# ZynqPower.net
KiCad netlist of a schematic drawn in Altium Designer
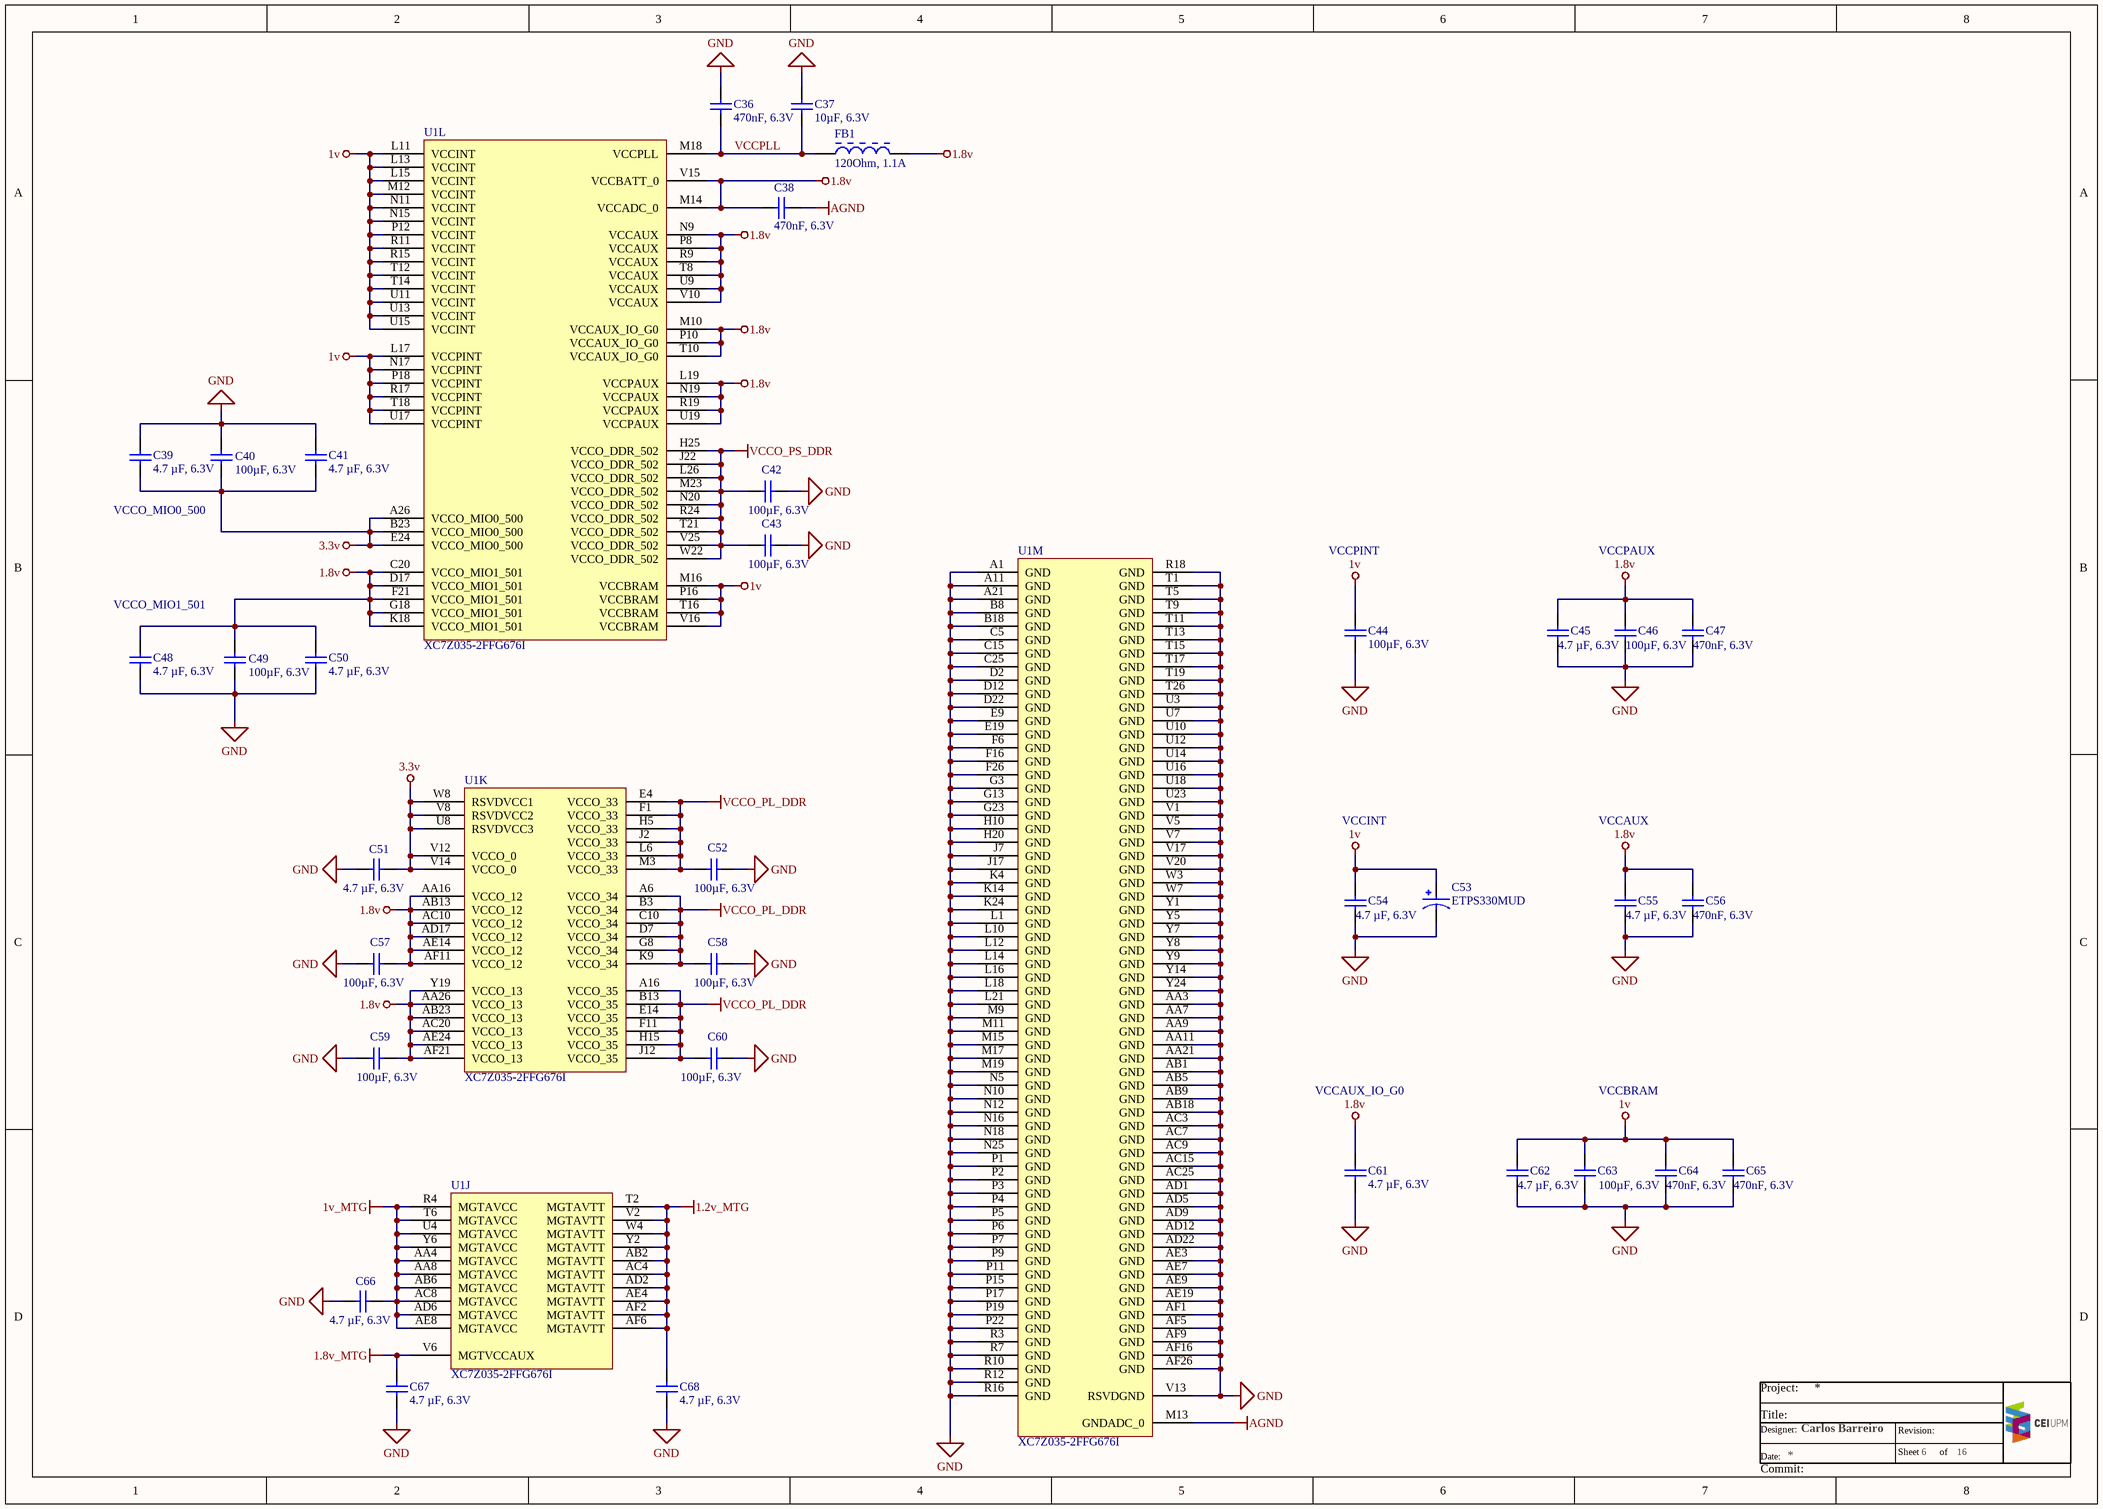
[diagram p0: ZynqPower.SchDoc]

(export (version "E")
  (design (tool "Eeschema 10.0.6"))
  (components
    (comp (ref "C36")
      (value "470nF, 6.3V")
      (footprint "WURTH_WCAP-CSGP_0402")
      (description "WCAP-CSGP Multilayer Ceramic Chip Capacitor, General Purpose, size 0402, X5R, 470nF, 6.3V")
      (fields
        (field (name "MANUFACTURER PART NUMBER") "885012105004")
        (field (name "MANUFACTURER") "Wurth Elektronik")
      )
      (libsource (lib "SpaceVNX") (part "885012105004"))
    )
    (comp (ref "C37")
      (value "10µF, 6.3V")
      (footprint "WURTH_WCAP-CSGP_0402")
      (description "WCAP-CSGP Multilayer Ceramic Chip Capacitor, General Purpose, size 0402, X5R, 10uF, 6.3V")
      (fields
        (field (name "MANUFACTURER PART NUMBER") "885012105020")
        (field (name "MANUFACTURER") "Wurth Elektronik")
      )
      (libsource (lib "SpaceVNX") (part "885012105020"))
    )
    (comp (ref "C38")
      (value "470nF, 6.3V")
      (footprint "WURTH_WCAP-CSGP_0402")
      (description "WCAP-CSGP Multilayer Ceramic Chip Capacitor, General Purpose, size 0402, X5R, 470nF, 6.3V")
      (fields
        (field (name "MANUFACTURER PART NUMBER") "885012105004")
        (field (name "MANUFACTURER") "Wurth Elektronik")
      )
      (libsource (lib "SpaceVNX") (part "885012105004"))
    )
    (comp (ref "C39")
      (value "4.7 µF, 6.3V")
      (footprint "WURTH_WCAP-CSGP_0402")
      (description "Multilayer Ceramic Capacitors MLCC, size 0402, X5R, 4.7 µF, 6.3V")
      (fields
        (field (name "MANUFACTURER PART NUMBER") "GRM155C80J475MEAAD")
        (field (name "MANUFACTURER") "Murata")
      )
      (libsource (lib "SpaceVNX") (part "GRM155C80J475MEAAD"))
    )
    (comp (ref "C40")
      (value "100µF, 6.3V")
      (footprint "WURTH_WCAP-CSGP_1206_H=1.6mm")
      (description "WCAP-CSGP Multilayer Ceramic Chip Capacitor, General Purpose, size 1206, X5R, 100uF, 6.3V")
      (fields
        (field (name "MANUFACTURER PART NUMBER") "885012108005")
        (field (name "MANUFACTURER") "Wurth Elektronik")
      )
      (libsource (lib "SpaceVNX") (part "885012108005"))
    )
    (comp (ref "C41")
      (value "4.7 µF, 6.3V")
      (footprint "WURTH_WCAP-CSGP_0402")
      (description "Multilayer Ceramic Capacitors MLCC, size 0402, X5R, 4.7 µF, 6.3V")
      (fields
        (field (name "MANUFACTURER PART NUMBER") "GRM155C80J475MEAAD")
        (field (name "MANUFACTURER") "Murata")
      )
      (libsource (lib "SpaceVNX") (part "GRM155C80J475MEAAD"))
    )
    (comp (ref "C42")
      (value "100µF, 6.3V")
      (footprint "WURTH_WCAP-CSGP_1206_H=1.6mm")
      (description "WCAP-CSGP Multilayer Ceramic Chip Capacitor, General Purpose, size 1206, X5R, 100uF, 6.3V")
      (fields
        (field (name "MANUFACTURER PART NUMBER") "885012108005")
        (field (name "MANUFACTURER") "Wurth Elektronik")
      )
      (libsource (lib "SpaceVNX") (part "885012108005"))
    )
    (comp (ref "C43")
      (value "100µF, 6.3V")
      (footprint "WURTH_WCAP-CSGP_1206_H=1.6mm")
      (description "WCAP-CSGP Multilayer Ceramic Chip Capacitor, General Purpose, size 1206, X5R, 100uF, 6.3V")
      (fields
        (field (name "MANUFACTURER PART NUMBER") "885012108005")
        (field (name "MANUFACTURER") "Wurth Elektronik")
      )
      (libsource (lib "SpaceVNX") (part "885012108005"))
    )
    (comp (ref "C44")
      (value "100µF, 6.3V")
      (footprint "WURTH_WCAP-CSGP_1206_H=1.6mm")
      (description "WCAP-CSGP Multilayer Ceramic Chip Capacitor, General Purpose, size 1206, X5R, 100uF, 6.3V")
      (fields
        (field (name "MANUFACTURER PART NUMBER") "885012108005")
        (field (name "MANUFACTURER") "Wurth Elektronik")
      )
      (libsource (lib "SpaceVNX") (part "885012108005"))
    )
    (comp (ref "C45")
      (value "4.7 µF, 6.3V")
      (footprint "WURTH_WCAP-CSGP_0402")
      (description "Multilayer Ceramic Capacitors MLCC, size 0402, X5R, 4.7 µF, 6.3V")
      (fields
        (field (name "MANUFACTURER PART NUMBER") "GRM155C80J475MEAAD")
        (field (name "MANUFACTURER") "Murata")
      )
      (libsource (lib "SpaceVNX") (part "GRM155C80J475MEAAD"))
    )
    (comp (ref "C46")
      (value "100µF, 6.3V")
      (footprint "WURTH_WCAP-CSGP_1206_H=1.6mm")
      (description "WCAP-CSGP Multilayer Ceramic Chip Capacitor, General Purpose, size 1206, X5R, 100uF, 6.3V")
      (fields
        (field (name "MANUFACTURER PART NUMBER") "885012108005")
        (field (name "MANUFACTURER") "Wurth Elektronik")
      )
      (libsource (lib "SpaceVNX") (part "885012108005"))
    )
    (comp (ref "C47")
      (value "470nF, 6.3V")
      (footprint "WURTH_WCAP-CSGP_0402")
      (description "WCAP-CSGP Multilayer Ceramic Chip Capacitor, General Purpose, size 0402, X5R, 470nF, 6.3V")
      (fields
        (field (name "MANUFACTURER PART NUMBER") "885012105004")
        (field (name "MANUFACTURER") "Wurth Elektronik")
      )
      (libsource (lib "SpaceVNX") (part "885012105004"))
    )
    (comp (ref "C48")
      (value "4.7 µF, 6.3V")
      (footprint "WURTH_WCAP-CSGP_0402")
      (description "Multilayer Ceramic Capacitors MLCC, size 0402, X5R, 4.7 µF, 6.3V")
      (fields
        (field (name "MANUFACTURER PART NUMBER") "GRM155C80J475MEAAD")
        (field (name "MANUFACTURER") "Murata")
      )
      (libsource (lib "SpaceVNX") (part "GRM155C80J475MEAAD"))
    )
    (comp (ref "C49")
      (value "100µF, 6.3V")
      (footprint "WURTH_WCAP-CSGP_1206_H=1.6mm")
      (description "WCAP-CSGP Multilayer Ceramic Chip Capacitor, General Purpose, size 1206, X5R, 100uF, 6.3V")
      (fields
        (field (name "MANUFACTURER PART NUMBER") "885012108005")
        (field (name "MANUFACTURER") "Wurth Elektronik")
      )
      (libsource (lib "SpaceVNX") (part "885012108005"))
    )
    (comp (ref "C50")
      (value "4.7 µF, 6.3V")
      (footprint "WURTH_WCAP-CSGP_0402")
      (description "Multilayer Ceramic Capacitors MLCC, size 0402, X5R, 4.7 µF, 6.3V")
      (fields
        (field (name "MANUFACTURER PART NUMBER") "GRM155C80J475MEAAD")
        (field (name "MANUFACTURER") "Murata")
      )
      (libsource (lib "SpaceVNX") (part "GRM155C80J475MEAAD"))
    )
    (comp (ref "C51")
      (value "4.7 µF, 6.3V")
      (footprint "WURTH_WCAP-CSGP_0402")
      (description "Multilayer Ceramic Capacitors MLCC, size 0402, X5R, 4.7 µF, 6.3V")
      (fields
        (field (name "MANUFACTURER PART NUMBER") "GRM155C80J475MEAAD")
        (field (name "MANUFACTURER") "Murata")
      )
      (libsource (lib "SpaceVNX") (part "GRM155C80J475MEAAD"))
    )
    (comp (ref "C52")
      (value "100µF, 6.3V")
      (footprint "WURTH_WCAP-CSGP_1206_H=1.6mm")
      (description "WCAP-CSGP Multilayer Ceramic Chip Capacitor, General Purpose, size 1206, X5R, 100uF, 6.3V")
      (fields
        (field (name "MANUFACTURER PART NUMBER") "885012108005")
        (field (name "MANUFACTURER") "Wurth Elektronik")
      )
      (libsource (lib "SpaceVNX") (part "885012108005"))
    )
    (comp (ref "C53")
      (value "ETPS330MUD")
      (footprint "PANASONIC_B1S")
      (description "Conductive Polymer Tantalum Solid Capacitors")
      (fields (field (name "MF") "Panasonic"))
      (libsource (lib "SpaceVNX") (part "ETPS330MUD"))
    )
    (comp (ref "C54")
      (value "4.7 µF, 6.3V")
      (footprint "WURTH_WCAP-CSGP_0402")
      (description "Multilayer Ceramic Capacitors MLCC, size 0402, X5R, 4.7 µF, 6.3V")
      (fields
        (field (name "MANUFACTURER PART NUMBER") "GRM155C80J475MEAAD")
        (field (name "MANUFACTURER") "Murata")
      )
      (libsource (lib "SpaceVNX") (part "GRM155C80J475MEAAD"))
    )
    (comp (ref "C55")
      (value "4.7 µF, 6.3V")
      (footprint "WURTH_WCAP-CSGP_0402")
      (description "Multilayer Ceramic Capacitors MLCC, size 0402, X5R, 4.7 µF, 6.3V")
      (fields
        (field (name "MANUFACTURER PART NUMBER") "GRM155C80J475MEAAD")
        (field (name "MANUFACTURER") "Murata")
      )
      (libsource (lib "SpaceVNX") (part "GRM155C80J475MEAAD"))
    )
    (comp (ref "C56")
      (value "470nF, 6.3V")
      (footprint "WURTH_WCAP-CSGP_0402")
      (description "WCAP-CSGP Multilayer Ceramic Chip Capacitor, General Purpose, size 0402, X5R, 470nF, 6.3V")
      (fields
        (field (name "MANUFACTURER PART NUMBER") "885012105004")
        (field (name "MANUFACTURER") "Wurth Elektronik")
      )
      (libsource (lib "SpaceVNX") (part "885012105004"))
    )
    (comp (ref "C57")
      (value "100µF, 6.3V")
      (footprint "WURTH_WCAP-CSGP_1206_H=1.6mm")
      (description "WCAP-CSGP Multilayer Ceramic Chip Capacitor, General Purpose, size 1206, X5R, 100uF, 6.3V")
      (fields
        (field (name "MANUFACTURER PART NUMBER") "885012108005")
        (field (name "MANUFACTURER") "Wurth Elektronik")
      )
      (libsource (lib "SpaceVNX") (part "885012108005"))
    )
    (comp (ref "C58")
      (value "100µF, 6.3V")
      (footprint "WURTH_WCAP-CSGP_1206_H=1.6mm")
      (description "WCAP-CSGP Multilayer Ceramic Chip Capacitor, General Purpose, size 1206, X5R, 100uF, 6.3V")
      (fields
        (field (name "MANUFACTURER PART NUMBER") "885012108005")
        (field (name "MANUFACTURER") "Wurth Elektronik")
      )
      (libsource (lib "SpaceVNX") (part "885012108005"))
    )
    (comp (ref "C59")
      (value "100µF, 6.3V")
      (footprint "WURTH_WCAP-CSGP_1206_H=1.6mm")
      (description "WCAP-CSGP Multilayer Ceramic Chip Capacitor, General Purpose, size 1206, X5R, 100uF, 6.3V")
      (fields
        (field (name "MANUFACTURER PART NUMBER") "885012108005")
        (field (name "MANUFACTURER") "Wurth Elektronik")
      )
      (libsource (lib "SpaceVNX") (part "885012108005"))
    )
    (comp (ref "C60")
      (value "100µF, 6.3V")
      (footprint "WURTH_WCAP-CSGP_1206_H=1.6mm")
      (description "WCAP-CSGP Multilayer Ceramic Chip Capacitor, General Purpose, size 1206, X5R, 100uF, 6.3V")
      (fields
        (field (name "MANUFACTURER PART NUMBER") "885012108005")
        (field (name "MANUFACTURER") "Wurth Elektronik")
      )
      (libsource (lib "SpaceVNX") (part "885012108005"))
    )
    (comp (ref "C61")
      (value "4.7 µF, 6.3V")
      (footprint "WURTH_WCAP-CSGP_0402")
      (description "Multilayer Ceramic Capacitors MLCC, size 0402, X5R, 4.7 µF, 6.3V")
      (fields
        (field (name "MANUFACTURER PART NUMBER") "GRM155C80J475MEAAD")
        (field (name "MANUFACTURER") "Murata")
      )
      (libsource (lib "SpaceVNX") (part "GRM155C80J475MEAAD"))
    )
    (comp (ref "C62")
      (value "4.7 µF, 6.3V")
      (footprint "WURTH_WCAP-CSGP_0402")
      (description "Multilayer Ceramic Capacitors MLCC, size 0402, X5R, 4.7 µF, 6.3V")
      (fields
        (field (name "MANUFACTURER PART NUMBER") "GRM155C80J475MEAAD")
        (field (name "MANUFACTURER") "Murata")
      )
      (libsource (lib "SpaceVNX") (part "GRM155C80J475MEAAD"))
    )
    (comp (ref "C63")
      (value "100µF, 6.3V")
      (footprint "WURTH_WCAP-CSGP_1206_H=1.6mm")
      (description "WCAP-CSGP Multilayer Ceramic Chip Capacitor, General Purpose, size 1206, X5R, 100uF, 6.3V")
      (fields
        (field (name "MANUFACTURER PART NUMBER") "885012108005")
        (field (name "MANUFACTURER") "Wurth Elektronik")
      )
      (libsource (lib "SpaceVNX") (part "885012108005"))
    )
    (comp (ref "C64")
      (value "470nF, 6.3V")
      (footprint "WURTH_WCAP-CSGP_0402")
      (description "WCAP-CSGP Multilayer Ceramic Chip Capacitor, General Purpose, size 0402, X5R, 470nF, 6.3V")
      (fields
        (field (name "MANUFACTURER PART NUMBER") "885012105004")
        (field (name "MANUFACTURER") "Wurth Elektronik")
      )
      (libsource (lib "SpaceVNX") (part "885012105004"))
    )
    (comp (ref "C65")
      (value "470nF, 6.3V")
      (footprint "WURTH_WCAP-CSGP_0402")
      (description "WCAP-CSGP Multilayer Ceramic Chip Capacitor, General Purpose, size 0402, X5R, 470nF, 6.3V")
      (fields
        (field (name "MANUFACTURER PART NUMBER") "885012105004")
        (field (name "MANUFACTURER") "Wurth Elektronik")
      )
      (libsource (lib "SpaceVNX") (part "885012105004"))
    )
    (comp (ref "C66")
      (value "4.7 µF, 6.3V")
      (footprint "WURTH_WCAP-CSGP_0402")
      (description "Multilayer Ceramic Capacitors MLCC, size 0402, X5R, 4.7 µF, 6.3V")
      (fields
        (field (name "MANUFACTURER PART NUMBER") "GRM155C80J475MEAAD")
        (field (name "MANUFACTURER") "Murata")
      )
      (libsource (lib "SpaceVNX") (part "GRM155C80J475MEAAD"))
    )
    (comp (ref "C67")
      (value "4.7 µF, 6.3V")
      (footprint "WURTH_WCAP-CSGP_0402")
      (description "Multilayer Ceramic Capacitors MLCC, size 0402, X5R, 4.7 µF, 6.3V")
      (fields
        (field (name "MANUFACTURER PART NUMBER") "GRM155C80J475MEAAD")
        (field (name "MANUFACTURER") "Murata")
      )
      (libsource (lib "SpaceVNX") (part "GRM155C80J475MEAAD"))
    )
    (comp (ref "C68")
      (value "4.7 µF, 6.3V")
      (footprint "WURTH_WCAP-CSGP_0402")
      (description "Multilayer Ceramic Capacitors MLCC, size 0402, X5R, 4.7 µF, 6.3V")
      (fields
        (field (name "MANUFACTURER PART NUMBER") "GRM155C80J475MEAAD")
        (field (name "MANUFACTURER") "Murata")
      )
      (libsource (lib "SpaceVNX") (part "GRM155C80J475MEAAD"))
    )
    (comp (ref "FB1")
      (value "120Ohm, 1.1A")
      (footprint "WURTH-CBF_0402")
      (description "WE-CBF SMT EMI Suppression Ferrite Bead, size 0402, 120Ohm, 1.1A")
      (fields
        (field (name "MANUFACTURER PART NUMBER") "74279271")
        (field (name "MANUFACTURER") "Wurth Elektronik")
      )
      (libsource (lib "SpaceVNX") (part "74279271"))
    )
    (comp (ref "U1")
      (value "XC7Z035-2FFG676I")
      (footprint "XILINX_FBG676")
      (fields (field (name "PARTNUMBER") "XC7Z035-2FBG676I") (field (name "GENERIC PART NUMBER") "XC7Z035"))
      (libsource (lib "SpaceVNX") (part "XC7Z035-2FFG676I"))
    )
  )
  (nets
    (net (code "1") (name "/VCCPLL") (class "Default")
      (node (ref "C36") (pin "1") (pinfunction "1_1") (pintype "passive"))
      (node (ref "C37") (pin "1") (pinfunction "1_1") (pintype "passive"))
      (node (ref "FB1") (pin "1") (pinfunction "1_1") (pintype "passive"))
      (node (ref "U1") (pin "M18") (pinfunction "VCCPLL_M18") (pintype "power_in"))
    )
    (net (code "2") (name "1.2v_MTG") (class "Default")
      (node (ref "C68") (pin "2") (pinfunction "2_2") (pintype "passive"))
      (node (ref "U1") (pin "AB2") (pinfunction "MGTAVTT_AB2") (pintype "power_in"))
      (node (ref "U1") (pin "AC4") (pinfunction "MGTAVTT_AC4") (pintype "power_in"))
      (node (ref "U1") (pin "AD2") (pinfunction "MGTAVTT_AD2") (pintype "power_in"))
      (node (ref "U1") (pin "AE4") (pinfunction "MGTAVTT_AE4") (pintype "power_in"))
      (node (ref "U1") (pin "AF2") (pinfunction "MGTAVTT_AF2") (pintype "power_in"))
      (node (ref "U1") (pin "AF6") (pinfunction "MGTAVTT_AF6") (pintype "power_in"))
      (node (ref "U1") (pin "T2") (pinfunction "MGTAVTT_T2") (pintype "power_in"))
      (node (ref "U1") (pin "V2") (pinfunction "MGTAVTT_V2") (pintype "power_in"))
      (node (ref "U1") (pin "W4") (pinfunction "MGTAVTT_W4") (pintype "power_in"))
      (node (ref "U1") (pin "Y2") (pinfunction "MGTAVTT_Y2") (pintype "power_in"))
    )
    (net (code "3") (name "1.8v") (class "Default")
      (node (ref "C38") (pin "2") (pinfunction "2_2") (pintype "passive"))
      (node (ref "C45") (pin "1") (pinfunction "1_1") (pintype "passive"))
      (node (ref "C46") (pin "2") (pinfunction "2_2") (pintype "passive"))
      (node (ref "C47") (pin "2") (pinfunction "2_2") (pintype "passive"))
      (node (ref "C48") (pin "2") (pinfunction "2_2") (pintype "passive"))
      (node (ref "C49") (pin "1") (pinfunction "1_1") (pintype "passive"))
      (node (ref "C50") (pin "2") (pinfunction "2_2") (pintype "passive"))
      (node (ref "C55") (pin "2") (pinfunction "2_2") (pintype "passive"))
      (node (ref "C56") (pin "2") (pinfunction "2_2") (pintype "passive"))
      (node (ref "C57") (pin "1") (pinfunction "1_1") (pintype "passive"))
      (node (ref "C59") (pin "1") (pinfunction "1_1") (pintype "passive"))
      (node (ref "C61") (pin "2") (pinfunction "2_2") (pintype "passive"))
      (node (ref "FB1") (pin "2") (pinfunction "2_2") (pintype "passive"))
      (node (ref "U1") (pin "AA16") (pinfunction "VCCO_12_AA16") (pintype "power_in"))
      (node (ref "U1") (pin "AA26") (pinfunction "VCCO_13_AA26") (pintype "power_in"))
      (node (ref "U1") (pin "AB13") (pinfunction "VCCO_12_AB13") (pintype "power_in"))
      (node (ref "U1") (pin "AB23") (pinfunction "VCCO_13_AB23") (pintype "power_in"))
      (node (ref "U1") (pin "AC10") (pinfunction "VCCO_12_AC10") (pintype "power_in"))
      (node (ref "U1") (pin "AC20") (pinfunction "VCCO_13_AC20") (pintype "power_in"))
      (node (ref "U1") (pin "AD17") (pinfunction "VCCO_12_AD17") (pintype "power_in"))
      (node (ref "U1") (pin "AE14") (pinfunction "VCCO_12_AE14") (pintype "power_in"))
      (node (ref "U1") (pin "AE24") (pinfunction "VCCO_13_AE24") (pintype "power_in"))
      (node (ref "U1") (pin "AF11") (pinfunction "VCCO_12_AF11") (pintype "power_in"))
      (node (ref "U1") (pin "AF21") (pinfunction "VCCO_13_AF21") (pintype "power_in"))
      (node (ref "U1") (pin "C20") (pinfunction "VCCO_MIO1_501_C20") (pintype "power_in"))
      (node (ref "U1") (pin "D17") (pinfunction "VCCO_MIO1_501_D17") (pintype "power_in"))
      (node (ref "U1") (pin "F21") (pinfunction "VCCO_MIO1_501_F21") (pintype "power_in"))
      (node (ref "U1") (pin "G18") (pinfunction "VCCO_MIO1_501_G18") (pintype "power_in"))
      (node (ref "U1") (pin "K18") (pinfunction "VCCO_MIO1_501_K18") (pintype "power_in"))
      (node (ref "U1") (pin "L19") (pinfunction "VCCPAUX_L19") (pintype "power_in"))
      (node (ref "U1") (pin "M10") (pinfunction "VCCAUX_IO_G0_M10") (pintype "power_in"))
      (node (ref "U1") (pin "M14") (pinfunction "VCCADC_0_M14") (pintype "power_in"))
      (node (ref "U1") (pin "N19") (pinfunction "VCCPAUX_N19") (pintype "power_in"))
      (node (ref "U1") (pin "N9") (pinfunction "VCCAUX_N9") (pintype "power_in"))
      (node (ref "U1") (pin "P10") (pinfunction "VCCAUX_IO_G0_P10") (pintype "power_in"))
      (node (ref "U1") (pin "P8") (pinfunction "VCCAUX_P8") (pintype "power_in"))
      (node (ref "U1") (pin "R19") (pinfunction "VCCPAUX_R19") (pintype "power_in"))
      (node (ref "U1") (pin "R9") (pinfunction "VCCAUX_R9") (pintype "power_in"))
      (node (ref "U1") (pin "T10") (pinfunction "VCCAUX_IO_G0_T10") (pintype "power_in"))
      (node (ref "U1") (pin "T8") (pinfunction "VCCAUX_T8") (pintype "power_in"))
      (node (ref "U1") (pin "U19") (pinfunction "VCCPAUX_U19") (pintype "power_in"))
      (node (ref "U1") (pin "U9") (pinfunction "VCCAUX_U9") (pintype "power_in"))
      (node (ref "U1") (pin "V10") (pinfunction "VCCAUX_V10") (pintype "power_in"))
      (node (ref "U1") (pin "V15") (pinfunction "VCCBATT_0_V15") (pintype "power_in"))
      (node (ref "U1") (pin "Y19") (pinfunction "VCCO_13_Y19") (pintype "power_in"))
    )
    (net (code "4") (name "1.8v_MTG") (class "Default")
      (node (ref "C67") (pin "2") (pinfunction "2_2") (pintype "passive"))
      (node (ref "U1") (pin "V6") (pinfunction "MGTVCCAUX_V6") (pintype "power_in"))
    )
    (net (code "5") (name "1v") (class "Default")
      (node (ref "C44") (pin "2") (pinfunction "2_2") (pintype "passive"))
      (node (ref "C53") (pin "1") (pinfunction "1_1") (pintype "passive"))
      (node (ref "C54") (pin "1") (pinfunction "1_1") (pintype "passive"))
      (node (ref "C62") (pin "1") (pinfunction "1_1") (pintype "passive"))
      (node (ref "C63") (pin "2") (pinfunction "2_2") (pintype "passive"))
      (node (ref "C64") (pin "2") (pinfunction "2_2") (pintype "passive"))
      (node (ref "C65") (pin "2") (pinfunction "2_2") (pintype "passive"))
      (node (ref "U1") (pin "L11") (pinfunction "VCCINT_L11") (pintype "power_in"))
      (node (ref "U1") (pin "L13") (pinfunction "VCCINT_L13") (pintype "power_in"))
      (node (ref "U1") (pin "L15") (pinfunction "VCCINT_L15") (pintype "power_in"))
      (node (ref "U1") (pin "L17") (pinfunction "VCCPINT_L17") (pintype "power_in"))
      (node (ref "U1") (pin "M12") (pinfunction "VCCINT_M12") (pintype "power_in"))
      (node (ref "U1") (pin "M16") (pinfunction "VCCBRAM_M16") (pintype "power_in"))
      (node (ref "U1") (pin "N11") (pinfunction "VCCINT_N11") (pintype "power_in"))
      (node (ref "U1") (pin "N15") (pinfunction "VCCINT_N15") (pintype "power_in"))
      (node (ref "U1") (pin "N17") (pinfunction "VCCPINT_N17") (pintype "power_in"))
      (node (ref "U1") (pin "P12") (pinfunction "VCCINT_P12") (pintype "power_in"))
      (node (ref "U1") (pin "P16") (pinfunction "VCCBRAM_P16") (pintype "power_in"))
      (node (ref "U1") (pin "P18") (pinfunction "VCCPINT_P18") (pintype "power_in"))
      (node (ref "U1") (pin "R11") (pinfunction "VCCINT_R11") (pintype "power_in"))
      (node (ref "U1") (pin "R15") (pinfunction "VCCINT_R15") (pintype "power_in"))
      (node (ref "U1") (pin "R17") (pinfunction "VCCPINT_R17") (pintype "power_in"))
      (node (ref "U1") (pin "T12") (pinfunction "VCCINT_T12") (pintype "power_in"))
      (node (ref "U1") (pin "T14") (pinfunction "VCCINT_T14") (pintype "power_in"))
      (node (ref "U1") (pin "T16") (pinfunction "VCCBRAM_T16") (pintype "power_in"))
      (node (ref "U1") (pin "T18") (pinfunction "VCCPINT_T18") (pintype "power_in"))
      (node (ref "U1") (pin "U11") (pinfunction "VCCINT_U11") (pintype "power_in"))
      (node (ref "U1") (pin "U13") (pinfunction "VCCINT_U13") (pintype "power_in"))
      (node (ref "U1") (pin "U15") (pinfunction "VCCINT_U15") (pintype "power_in"))
      (node (ref "U1") (pin "U17") (pinfunction "VCCPINT_U17") (pintype "power_in"))
      (node (ref "U1") (pin "V16") (pinfunction "VCCBRAM_V16") (pintype "power_in"))
    )
    (net (code "6") (name "1v_MTG") (class "Default")
      (node (ref "C66") (pin "2") (pinfunction "2_2") (pintype "passive"))
      (node (ref "U1") (pin "AA4") (pinfunction "MGTAVCC_AA4") (pintype "power_in"))
      (node (ref "U1") (pin "AA8") (pinfunction "MGTAVCC_AA8") (pintype "power_in"))
      (node (ref "U1") (pin "AB6") (pinfunction "MGTAVCC_AB6") (pintype "power_in"))
      (node (ref "U1") (pin "AC8") (pinfunction "MGTAVCC_AC8") (pintype "power_in"))
      (node (ref "U1") (pin "AD6") (pinfunction "MGTAVCC_AD6") (pintype "power_in"))
      (node (ref "U1") (pin "AE8") (pinfunction "MGTAVCC_AE8") (pintype "power_in"))
      (node (ref "U1") (pin "R4") (pinfunction "MGTAVCC_R4") (pintype "power_in"))
      (node (ref "U1") (pin "T6") (pinfunction "MGTAVCC_T6") (pintype "power_in"))
      (node (ref "U1") (pin "U4") (pinfunction "MGTAVCC_U4") (pintype "power_in"))
      (node (ref "U1") (pin "Y6") (pinfunction "MGTAVCC_Y6") (pintype "power_in"))
    )
    (net (code "7") (name "3.3v") (class "Default")
      (node (ref "C39") (pin "2") (pinfunction "2_2") (pintype "passive"))
      (node (ref "C40") (pin "1") (pinfunction "1_1") (pintype "passive"))
      (node (ref "C41") (pin "2") (pinfunction "2_2") (pintype "passive"))
      (node (ref "C51") (pin "2") (pinfunction "2_2") (pintype "passive"))
      (node (ref "U1") (pin "A26") (pinfunction "VCCO_MIO0_500_A26") (pintype "power_in"))
      (node (ref "U1") (pin "B23") (pinfunction "VCCO_MIO0_500_B23") (pintype "power_in"))
      (node (ref "U1") (pin "E24") (pinfunction "VCCO_MIO0_500_E24") (pintype "power_in"))
      (node (ref "U1") (pin "U8") (pinfunction "RSVDVCC3_U8") (pintype "power_in"))
      (node (ref "U1") (pin "V12") (pinfunction "VCCO_0_V12") (pintype "power_in"))
      (node (ref "U1") (pin "V14") (pinfunction "VCCO_0_V14") (pintype "power_in"))
      (node (ref "U1") (pin "V8") (pinfunction "RSVDVCC2_V8") (pintype "power_in"))
      (node (ref "U1") (pin "W8") (pinfunction "RSVDVCC1_W8") (pintype "power_in"))
    )
    (net (code "8") (name "AGND") (class "Default")
      (node (ref "C38") (pin "1") (pinfunction "1_1") (pintype "passive"))
      (node (ref "U1") (pin "M13") (pinfunction "GNDADC_0_M13") (pintype "power_in"))
    )
    (net (code "9") (name "GND") (class "Default")
      (node (ref "C36") (pin "2") (pinfunction "2_2") (pintype "passive"))
      (node (ref "C37") (pin "2") (pinfunction "2_2") (pintype "passive"))
      (node (ref "C39") (pin "1") (pinfunction "1_1") (pintype "passive"))
      (node (ref "C40") (pin "2") (pinfunction "2_2") (pintype "passive"))
      (node (ref "C41") (pin "1") (pinfunction "1_1") (pintype "passive"))
      (node (ref "C42") (pin "2") (pinfunction "2_2") (pintype "passive"))
      (node (ref "C43") (pin "2") (pinfunction "2_2") (pintype "passive"))
      (node (ref "C44") (pin "1") (pinfunction "1_1") (pintype "passive"))
      (node (ref "C45") (pin "2") (pinfunction "2_2") (pintype "passive"))
      (node (ref "C46") (pin "1") (pinfunction "1_1") (pintype "passive"))
      (node (ref "C47") (pin "1") (pinfunction "1_1") (pintype "passive"))
      (node (ref "C48") (pin "1") (pinfunction "1_1") (pintype "passive"))
      (node (ref "C49") (pin "2") (pinfunction "2_2") (pintype "passive"))
      (node (ref "C50") (pin "1") (pinfunction "1_1") (pintype "passive"))
      (node (ref "C51") (pin "1") (pinfunction "1_1") (pintype "passive"))
      (node (ref "C52") (pin "2") (pinfunction "2_2") (pintype "passive"))
      (node (ref "C53") (pin "2") (pinfunction "2_2") (pintype "passive"))
      (node (ref "C54") (pin "2") (pinfunction "2_2") (pintype "passive"))
      (node (ref "C55") (pin "1") (pinfunction "1_1") (pintype "passive"))
      (node (ref "C56") (pin "1") (pinfunction "1_1") (pintype "passive"))
      (node (ref "C57") (pin "2") (pinfunction "2_2") (pintype "passive"))
      (node (ref "C58") (pin "2") (pinfunction "2_2") (pintype "passive"))
      (node (ref "C59") (pin "2") (pinfunction "2_2") (pintype "passive"))
      (node (ref "C60") (pin "2") (pinfunction "2_2") (pintype "passive"))
      (node (ref "C61") (pin "1") (pinfunction "1_1") (pintype "passive"))
      (node (ref "C62") (pin "2") (pinfunction "2_2") (pintype "passive"))
      (node (ref "C63") (pin "1") (pinfunction "1_1") (pintype "passive"))
      (node (ref "C64") (pin "1") (pinfunction "1_1") (pintype "passive"))
      (node (ref "C65") (pin "1") (pinfunction "1_1") (pintype "passive"))
      (node (ref "C66") (pin "1") (pinfunction "1_1") (pintype "passive"))
      (node (ref "C67") (pin "1") (pinfunction "1_1") (pintype "passive"))
      (node (ref "C68") (pin "1") (pinfunction "1_1") (pintype "passive"))
      (node (ref "U1") (pin "A1") (pinfunction "GND_A1") (pintype "power_in"))
      (node (ref "U1") (pin "A11") (pinfunction "GND_A11") (pintype "power_in"))
      (node (ref "U1") (pin "A21") (pinfunction "GND_A21") (pintype "power_in"))
      (node (ref "U1") (pin "AA11") (pinfunction "GND_AA11") (pintype "power_in"))
      (node (ref "U1") (pin "AA21") (pinfunction "GND_AA21") (pintype "power_in"))
      (node (ref "U1") (pin "AA3") (pinfunction "GND_AA3") (pintype "power_in"))
      (node (ref "U1") (pin "AA7") (pinfunction "GND_AA7") (pintype "power_in"))
      (node (ref "U1") (pin "AA9") (pinfunction "GND_AA9") (pintype "power_in"))
      (node (ref "U1") (pin "AB1") (pinfunction "GND_AB1") (pintype "power_in"))
      (node (ref "U1") (pin "AB18") (pinfunction "GND_AB18") (pintype "power_in"))
      (node (ref "U1") (pin "AB5") (pinfunction "GND_AB5") (pintype "power_in"))
      (node (ref "U1") (pin "AB9") (pinfunction "GND_AB9") (pintype "power_in"))
      (node (ref "U1") (pin "AC15") (pinfunction "GND_AC15") (pintype "power_in"))
      (node (ref "U1") (pin "AC25") (pinfunction "GND_AC25") (pintype "power_in"))
      (node (ref "U1") (pin "AC3") (pinfunction "GND_AC3") (pintype "power_in"))
      (node (ref "U1") (pin "AC7") (pinfunction "GND_AC7") (pintype "power_in"))
      (node (ref "U1") (pin "AC9") (pinfunction "GND_AC9") (pintype "power_in"))
      (node (ref "U1") (pin "AD1") (pinfunction "GND_AD1") (pintype "power_in"))
      (node (ref "U1") (pin "AD12") (pinfunction "GND_AD12") (pintype "power_in"))
      (node (ref "U1") (pin "AD22") (pinfunction "GND_AD22") (pintype "power_in"))
      (node (ref "U1") (pin "AD5") (pinfunction "GND_AD5") (pintype "power_in"))
      (node (ref "U1") (pin "AD9") (pinfunction "GND_AD9") (pintype "power_in"))
      (node (ref "U1") (pin "AE19") (pinfunction "GND_AE19") (pintype "power_in"))
      (node (ref "U1") (pin "AE3") (pinfunction "GND_AE3") (pintype "power_in"))
      (node (ref "U1") (pin "AE7") (pinfunction "GND_AE7") (pintype "power_in"))
      (node (ref "U1") (pin "AE9") (pinfunction "GND_AE9") (pintype "power_in"))
      (node (ref "U1") (pin "AF1") (pinfunction "GND_AF1") (pintype "power_in"))
      (node (ref "U1") (pin "AF16") (pinfunction "GND_AF16") (pintype "power_in"))
      (node (ref "U1") (pin "AF26") (pinfunction "GND_AF26") (pintype "power_in"))
      (node (ref "U1") (pin "AF5") (pinfunction "GND_AF5") (pintype "power_in"))
      (node (ref "U1") (pin "AF9") (pinfunction "GND_AF9") (pintype "power_in"))
      (node (ref "U1") (pin "B18") (pinfunction "GND_B18") (pintype "power_in"))
      (node (ref "U1") (pin "B8") (pinfunction "GND_B8") (pintype "power_in"))
      (node (ref "U1") (pin "C15") (pinfunction "GND_C15") (pintype "power_in"))
      (node (ref "U1") (pin "C25") (pinfunction "GND_C25") (pintype "power_in"))
      (node (ref "U1") (pin "C5") (pinfunction "GND_C5") (pintype "power_in"))
      (node (ref "U1") (pin "D12") (pinfunction "GND_D12") (pintype "power_in"))
      (node (ref "U1") (pin "D2") (pinfunction "GND_D2") (pintype "power_in"))
      (node (ref "U1") (pin "D22") (pinfunction "GND_D22") (pintype "power_in"))
      (node (ref "U1") (pin "E19") (pinfunction "GND_E19") (pintype "power_in"))
      (node (ref "U1") (pin "E9") (pinfunction "GND_E9") (pintype "power_in"))
      (node (ref "U1") (pin "F16") (pinfunction "GND_F16") (pintype "power_in"))
      (node (ref "U1") (pin "F26") (pinfunction "GND_F26") (pintype "power_in"))
      (node (ref "U1") (pin "F6") (pinfunction "GND_F6") (pintype "power_in"))
      (node (ref "U1") (pin "G13") (pinfunction "GND_G13") (pintype "power_in"))
      (node (ref "U1") (pin "G23") (pinfunction "GND_G23") (pintype "power_in"))
      (node (ref "U1") (pin "G3") (pinfunction "GND_G3") (pintype "power_in"))
      (node (ref "U1") (pin "H10") (pinfunction "GND_H10") (pintype "power_in"))
      (node (ref "U1") (pin "H20") (pinfunction "GND_H20") (pintype "power_in"))
      (node (ref "U1") (pin "J17") (pinfunction "GND_J17") (pintype "power_in"))
      (node (ref "U1") (pin "J7") (pinfunction "GND_J7") (pintype "power_in"))
      (node (ref "U1") (pin "K14") (pinfunction "GND_K14") (pintype "power_in"))
      (node (ref "U1") (pin "K24") (pinfunction "GND_K24") (pintype "power_in"))
      (node (ref "U1") (pin "K4") (pinfunction "GND_K4") (pintype "power_in"))
      (node (ref "U1") (pin "L1") (pinfunction "GND_L1") (pintype "power_in"))
      (node (ref "U1") (pin "L10") (pinfunction "GND_L10") (pintype "power_in"))
      (node (ref "U1") (pin "L12") (pinfunction "GND_L12") (pintype "power_in"))
      (node (ref "U1") (pin "L14") (pinfunction "GND_L14") (pintype "power_in"))
      (node (ref "U1") (pin "L16") (pinfunction "GND_L16") (pintype "power_in"))
      (node (ref "U1") (pin "L18") (pinfunction "GND_L18") (pintype "power_in"))
      (node (ref "U1") (pin "L21") (pinfunction "GND_L21") (pintype "power_in"))
      (node (ref "U1") (pin "M11") (pinfunction "GND_M11") (pintype "power_in"))
      (node (ref "U1") (pin "M15") (pinfunction "GND_M15") (pintype "power_in"))
      (node (ref "U1") (pin "M17") (pinfunction "GND_M17") (pintype "power_in"))
      (node (ref "U1") (pin "M19") (pinfunction "GND_M19") (pintype "power_in"))
      (node (ref "U1") (pin "M9") (pinfunction "GND_M9") (pintype "power_in"))
      (node (ref "U1") (pin "N10") (pinfunction "GND_N10") (pintype "power_in"))
      (node (ref "U1") (pin "N12") (pinfunction "GND_N12") (pintype "power_in"))
      (node (ref "U1") (pin "N16") (pinfunction "GND_N16") (pintype "power_in"))
      (node (ref "U1") (pin "N18") (pinfunction "GND_N18") (pintype "power_in"))
      (node (ref "U1") (pin "N25") (pinfunction "GND_N25") (pintype "power_in"))
      (node (ref "U1") (pin "N5") (pinfunction "GND_N5") (pintype "power_in"))
      (node (ref "U1") (pin "P1") (pinfunction "GND_P1") (pintype "power_in"))
      (node (ref "U1") (pin "P11") (pinfunction "GND_P11") (pintype "power_in"))
      (node (ref "U1") (pin "P15") (pinfunction "GND_P15") (pintype "power_in"))
      (node (ref "U1") (pin "P17") (pinfunction "GND_P17") (pintype "power_in"))
      (node (ref "U1") (pin "P19") (pinfunction "GND_P19") (pintype "power_in"))
      (node (ref "U1") (pin "P2") (pinfunction "GND_P2") (pintype "power_in"))
      (node (ref "U1") (pin "P22") (pinfunction "GND_P22") (pintype "power_in"))
      (node (ref "U1") (pin "P3") (pinfunction "GND_P3") (pintype "power_in"))
      (node (ref "U1") (pin "P4") (pinfunction "GND_P4") (pintype "power_in"))
      (node (ref "U1") (pin "P5") (pinfunction "GND_P5") (pintype "power_in"))
      (node (ref "U1") (pin "P6") (pinfunction "GND_P6") (pintype "power_in"))
      (node (ref "U1") (pin "P7") (pinfunction "GND_P7") (pintype "power_in"))
      (node (ref "U1") (pin "P9") (pinfunction "GND_P9") (pintype "power_in"))
      (node (ref "U1") (pin "R10") (pinfunction "GND_R10") (pintype "power_in"))
      (node (ref "U1") (pin "R12") (pinfunction "GND_R12") (pintype "power_in"))
      (node (ref "U1") (pin "R16") (pinfunction "GND_R16") (pintype "power_in"))
      (node (ref "U1") (pin "R18") (pinfunction "GND_R18") (pintype "power_in"))
      (node (ref "U1") (pin "R3") (pinfunction "GND_R3") (pintype "power_in"))
      (node (ref "U1") (pin "R7") (pinfunction "GND_R7") (pintype "power_in"))
      (node (ref "U1") (pin "T1") (pinfunction "GND_T1") (pintype "power_in"))
      (node (ref "U1") (pin "T11") (pinfunction "GND_T11") (pintype "power_in"))
      (node (ref "U1") (pin "T13") (pinfunction "GND_T13") (pintype "power_in"))
      (node (ref "U1") (pin "T15") (pinfunction "GND_T15") (pintype "power_in"))
      (node (ref "U1") (pin "T17") (pinfunction "GND_T17") (pintype "power_in"))
      (node (ref "U1") (pin "T19") (pinfunction "GND_T19") (pintype "power_in"))
      (node (ref "U1") (pin "T26") (pinfunction "GND_T26") (pintype "power_in"))
      (node (ref "U1") (pin "T5") (pinfunction "GND_T5") (pintype "power_in"))
      (node (ref "U1") (pin "T9") (pinfunction "GND_T9") (pintype "power_in"))
      (node (ref "U1") (pin "U10") (pinfunction "GND_U10") (pintype "power_in"))
      (node (ref "U1") (pin "U12") (pinfunction "GND_U12") (pintype "power_in"))
      (node (ref "U1") (pin "U14") (pinfunction "GND_U14") (pintype "power_in"))
      (node (ref "U1") (pin "U16") (pinfunction "GND_U16") (pintype "power_in"))
      (node (ref "U1") (pin "U18") (pinfunction "GND_U18") (pintype "power_in"))
      (node (ref "U1") (pin "U23") (pinfunction "GND_U23") (pintype "power_in"))
      (node (ref "U1") (pin "U3") (pinfunction "GND_U3") (pintype "power_in"))
      (node (ref "U1") (pin "U7") (pinfunction "GND_U7") (pintype "power_in"))
      (node (ref "U1") (pin "V1") (pinfunction "GND_V1") (pintype "power_in"))
      (node (ref "U1") (pin "V13") (pinfunction "RSVDGND_V13") (pintype "power_in"))
      (node (ref "U1") (pin "V17") (pinfunction "GND_V17") (pintype "power_in"))
      (node (ref "U1") (pin "V20") (pinfunction "GND_V20") (pintype "power_in"))
      (node (ref "U1") (pin "V5") (pinfunction "GND_V5") (pintype "power_in"))
      (node (ref "U1") (pin "V7") (pinfunction "GND_V7") (pintype "power_in"))
      (node (ref "U1") (pin "W3") (pinfunction "GND_W3") (pintype "power_in"))
      (node (ref "U1") (pin "W7") (pinfunction "GND_W7") (pintype "power_in"))
      (node (ref "U1") (pin "Y1") (pinfunction "GND_Y1") (pintype "power_in"))
      (node (ref "U1") (pin "Y14") (pinfunction "GND_Y14") (pintype "power_in"))
      (node (ref "U1") (pin "Y24") (pinfunction "GND_Y24") (pintype "power_in"))
      (node (ref "U1") (pin "Y5") (pinfunction "GND_Y5") (pintype "power_in"))
      (node (ref "U1") (pin "Y7") (pinfunction "GND_Y7") (pintype "power_in"))
      (node (ref "U1") (pin "Y8") (pinfunction "GND_Y8") (pintype "power_in"))
      (node (ref "U1") (pin "Y9") (pinfunction "GND_Y9") (pintype "power_in"))
    )
    (net (code "10") (name "VCCO_PL_DDR") (class "Default")
      (node (ref "C52") (pin "1") (pinfunction "1_1") (pintype "passive"))
      (node (ref "C58") (pin "1") (pinfunction "1_1") (pintype "passive"))
      (node (ref "C60") (pin "1") (pinfunction "1_1") (pintype "passive"))
      (node (ref "U1") (pin "A16") (pinfunction "VCCO_35_A16") (pintype "power_in"))
      (node (ref "U1") (pin "A6") (pinfunction "VCCO_34_A6") (pintype "power_in"))
      (node (ref "U1") (pin "B13") (pinfunction "VCCO_35_B13") (pintype "power_in"))
      (node (ref "U1") (pin "B3") (pinfunction "VCCO_34_B3") (pintype "power_in"))
      (node (ref "U1") (pin "C10") (pinfunction "VCCO_34_C10") (pintype "power_in"))
      (node (ref "U1") (pin "D7") (pinfunction "VCCO_34_D7") (pintype "power_in"))
      (node (ref "U1") (pin "E14") (pinfunction "VCCO_35_E14") (pintype "power_in"))
      (node (ref "U1") (pin "E4") (pinfunction "VCCO_33_E4") (pintype "power_in"))
      (node (ref "U1") (pin "F1") (pinfunction "VCCO_33_F1") (pintype "power_in"))
      (node (ref "U1") (pin "F11") (pinfunction "VCCO_35_F11") (pintype "power_in"))
      (node (ref "U1") (pin "G8") (pinfunction "VCCO_34_G8") (pintype "power_in"))
      (node (ref "U1") (pin "H15") (pinfunction "VCCO_35_H15") (pintype "power_in"))
      (node (ref "U1") (pin "H5") (pinfunction "VCCO_33_H5") (pintype "power_in"))
      (node (ref "U1") (pin "J12") (pinfunction "VCCO_35_J12") (pintype "power_in"))
      (node (ref "U1") (pin "J2") (pinfunction "VCCO_33_J2") (pintype "power_in"))
      (node (ref "U1") (pin "K9") (pinfunction "VCCO_34_K9") (pintype "power_in"))
      (node (ref "U1") (pin "L6") (pinfunction "VCCO_33_L6") (pintype "power_in"))
      (node (ref "U1") (pin "M3") (pinfunction "VCCO_33_M3") (pintype "power_in"))
    )
    (net (code "11") (name "VCCO_PS_DDR") (class "Default")
      (node (ref "C42") (pin "1") (pinfunction "1_1") (pintype "passive"))
      (node (ref "C43") (pin "1") (pinfunction "1_1") (pintype "passive"))
      (node (ref "U1") (pin "H25") (pinfunction "VCCO_DDR_502_H25") (pintype "power_in"))
      (node (ref "U1") (pin "J22") (pinfunction "VCCO_DDR_502_J22") (pintype "power_in"))
      (node (ref "U1") (pin "L26") (pinfunction "VCCO_DDR_502_L26") (pintype "power_in"))
      (node (ref "U1") (pin "M23") (pinfunction "VCCO_DDR_502_M23") (pintype "power_in"))
      (node (ref "U1") (pin "N20") (pinfunction "VCCO_DDR_502_N20") (pintype "power_in"))
      (node (ref "U1") (pin "R24") (pinfunction "VCCO_DDR_502_R24") (pintype "power_in"))
      (node (ref "U1") (pin "T21") (pinfunction "VCCO_DDR_502_T21") (pintype "power_in"))
      (node (ref "U1") (pin "V25") (pinfunction "VCCO_DDR_502_V25") (pintype "power_in"))
      (node (ref "U1") (pin "W22") (pinfunction "VCCO_DDR_502_W22") (pintype "power_in"))
    )
  )
)
